# danger_danger_psu-mk-3.net
KiCad netlist of a schematic drawn in EAGLE
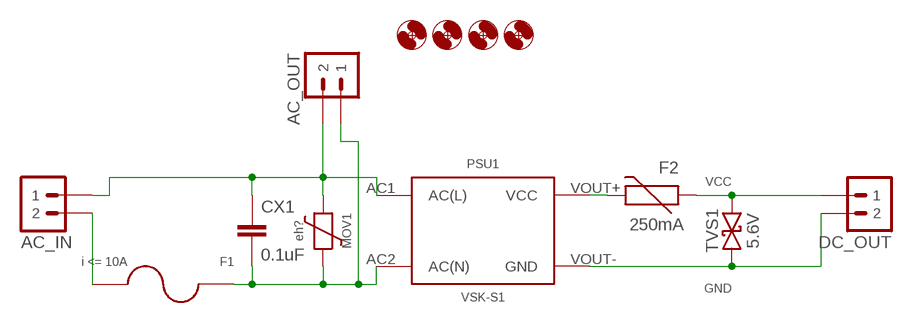
[diagram p0: schematic, sheet 1]

(export (version "E")
  (design (tool "Eeschema 10.0.6"))
  (components
    (comp (ref "AC_IN")
      (value "M023.5MM")
      (footprint "eagle-import:SCREWTERMINAL-3.5MM-2")
      (libsource (lib "eagle-import") (part "M023.5MM"))
    )
    (comp (ref "AC_OUT")
      (value "M023.5MM")
      (footprint "eagle-import:SCREWTERMINAL-3.5MM-2")
      (libsource (lib "eagle-import") (part "M023.5MM"))
    )
    (comp (ref "CX1")
      (value "0.1uF")
      (footprint "eagle-import:XC10B5")
      (libsource (lib "eagle-import") (part "CXXC10B5"))
    )
    (comp (ref "DC_OUT")
      (value "M02JST-PTH-VERT")
      (footprint "eagle-import:JST-2-PH-VERT-PTH")
      (libsource (lib "eagle-import") (part "M02JST-PTH-VERT"))
    )
    (comp (ref "F1")
      (value "i <= 10A")
      (footprint "eagle-import:FUSE-2AG")
      (libsource (lib "eagle-import") (part "FUSE5X20MM-2"))
    )
    (comp (ref "F2")
      (value "250mA")
      (footprint "eagle-import:PTC")
      (libsource (lib "eagle-import") (part "PTCPTH"))
    )
    (comp (ref "H1")
      (value "HOLE#2")
      (footprint "eagle-import:HOLE-#2")
      (libsource (lib "eagle-import") (part "HOLE#2"))
    )
    (comp (ref "H2")
      (value "HOLE#2")
      (footprint "eagle-import:HOLE-#2")
      (libsource (lib "eagle-import") (part "HOLE#2"))
    )
    (comp (ref "H3")
      (value "HOLE#2")
      (footprint "eagle-import:HOLE-#2")
      (libsource (lib "eagle-import") (part "HOLE#2"))
    )
    (comp (ref "H4")
      (value "HOLE#2")
      (footprint "eagle-import:HOLE-#2")
      (libsource (lib "eagle-import") (part "HOLE#2"))
    )
    (comp (ref "MOV1")
      (value "eh?")
      (footprint "eagle-import:VAR-5.08MM-PTH")
      (libsource (lib "eagle-import") (part "VARISITORVAR-5.08MM-PTH"))
    )
    (comp (ref "PSU1")
      (value "VSK-S1")
      (footprint "eagle-import:VSK-S1")
      (libsource (lib "eagle-import") (part "VSK-S1"))
    )
    (comp (ref "TVS1")
      (value "5.6V")
      (footprint "eagle-import:DO-41-TVS-BI-10.16MM")
      (libsource (lib "eagle-import") (part "TVSDO-41-10.16MM"))
    )
  )
  (nets
    (net (code "1") (name "/GND") (class "Default")
      (node (ref "DC_OUT") (pin "2") (pinfunction "2_2") (pintype "passive"))
      (node (ref "PSU1") (pin "VOUT-") (pinfunction "GND_VOUT-") (pintype "bidirectional"))
      (node (ref "TVS1") (pin "P$2") (pinfunction "2_P$2") (pintype "passive"))
    )
    (net (code "2") (name "/VCC") (class "Default")
      (node (ref "DC_OUT") (pin "1") (pinfunction "1_1") (pintype "passive"))
      (node (ref "F2") (pin "P$1") (pinfunction "1_P$1") (pintype "bidirectional"))
      (node (ref "TVS1") (pin "P$1") (pinfunction "1_P$1") (pintype "passive"))
    )
    (net (code "3") (name "Net-(AC_IN-Pad2)") (class "Default")
      (node (ref "AC_IN") (pin "2") (pinfunction "2_2") (pintype "passive"))
      (node (ref "F1") (pin "2") (pinfunction "2_2") (pintype "bidirectional"))
      (node (ref "F1") (pin "2@2") (pinfunction "2_2@2") (pintype "bidirectional"))
    )
    (net (code "4") (name "Net-(F2-2)") (class "Default")
      (node (ref "F2") (pin "P$2") (pinfunction "2_P$2") (pintype "bidirectional"))
      (node (ref "PSU1") (pin "VOUT+") (pinfunction "VCC_VOUT+") (pintype "bidirectional"))
    )
    (net (code "5") (name "Net-(MOV1-P$1)") (class "Default")
      (node (ref "AC_IN") (pin "1") (pinfunction "1_1") (pintype "passive"))
      (node (ref "AC_OUT") (pin "2") (pinfunction "2_2") (pintype "passive"))
      (node (ref "CX1") (pin "1") (pinfunction "1_1") (pintype "passive"))
      (node (ref "MOV1") (pin "1") (pinfunction "P$1_1") (pintype "bidirectional"))
      (node (ref "PSU1") (pin "AC1") (pinfunction "AC(L)_AC1") (pintype "bidirectional"))
    )
    (net (code "6") (name "Net-(MOV1-P$2)") (class "Default")
      (node (ref "AC_OUT") (pin "1") (pinfunction "1_1") (pintype "passive"))
      (node (ref "CX1") (pin "2") (pinfunction "2_2") (pintype "passive"))
      (node (ref "F1") (pin "1") (pinfunction "1_1") (pintype "bidirectional"))
      (node (ref "F1") (pin "1@1") (pinfunction "1_1@1") (pintype "bidirectional"))
      (node (ref "MOV1") (pin "2") (pinfunction "P$2_2") (pintype "bidirectional"))
      (node (ref "PSU1") (pin "AC2") (pinfunction "AC(N)_AC2") (pintype "bidirectional"))
    )
  )
)
